# BatteryHolderSMD_CR1220.net
KiCad netlist of a schematic drawn in EAGLE
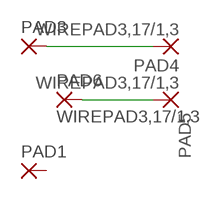
[diagram p0: schematic, sheet 1]

(export (version "E")
  (design (tool "Eeschema 10.0.6"))
  (components
    (comp (ref "PAD1")
      (value "SMD5")
      (footprint "eagle-import:SMD2,54-5,08")
      (libsource (lib "eagle-import") (part "SMD5"))
    )
    (comp (ref "PAD3")
      (value "SMD5")
      (footprint "eagle-import:SMD2,54-5,08")
      (libsource (lib "eagle-import") (part "SMD5"))
    )
    (comp (ref "PAD4")
      (value "WIREPAD3,17/1,3")
      (footprint "eagle-import:3,17_1,3")
      (libsource (lib "eagle-import") (part "WIREPAD3,17/1,3"))
    )
    (comp (ref "PAD5")
      (value "WIREPAD3,17/1,3")
      (footprint "eagle-import:3,17_1,3")
      (libsource (lib "eagle-import") (part "WIREPAD3,17/1,3"))
    )
    (comp (ref "PAD6")
      (value "WIREPAD3,17/1,3")
      (footprint "eagle-import:3,17_1,3")
      (libsource (lib "eagle-import") (part "WIREPAD3,17/1,3"))
    )
  )
  (nets
    (net (code "1") (name "Net-(PAD3-P)") (class "Default")
      (node (ref "PAD3") (pin "1") (pinfunction "P_1") (pintype "passive"))
      (node (ref "PAD4") (pin "1") (pinfunction "P_1") (pintype "passive"))
    )
    (net (code "2") (name "Net-(PAD5-P)") (class "Default")
      (node (ref "PAD5") (pin "1") (pinfunction "P_1") (pintype "passive"))
      (node (ref "PAD6") (pin "1") (pinfunction "P_1") (pintype "passive"))
    )
    (net (code "3") (name "unconnected-(PAD1-P-Pad1)") (class "Default")
      (node (ref "PAD1") (pin "1") (pinfunction "P_1") (pintype "passive"))
    )
  )
)
